# SCH_d_01_ex_01.net
KiCad netlist of a schematic drawn in EasyEDA
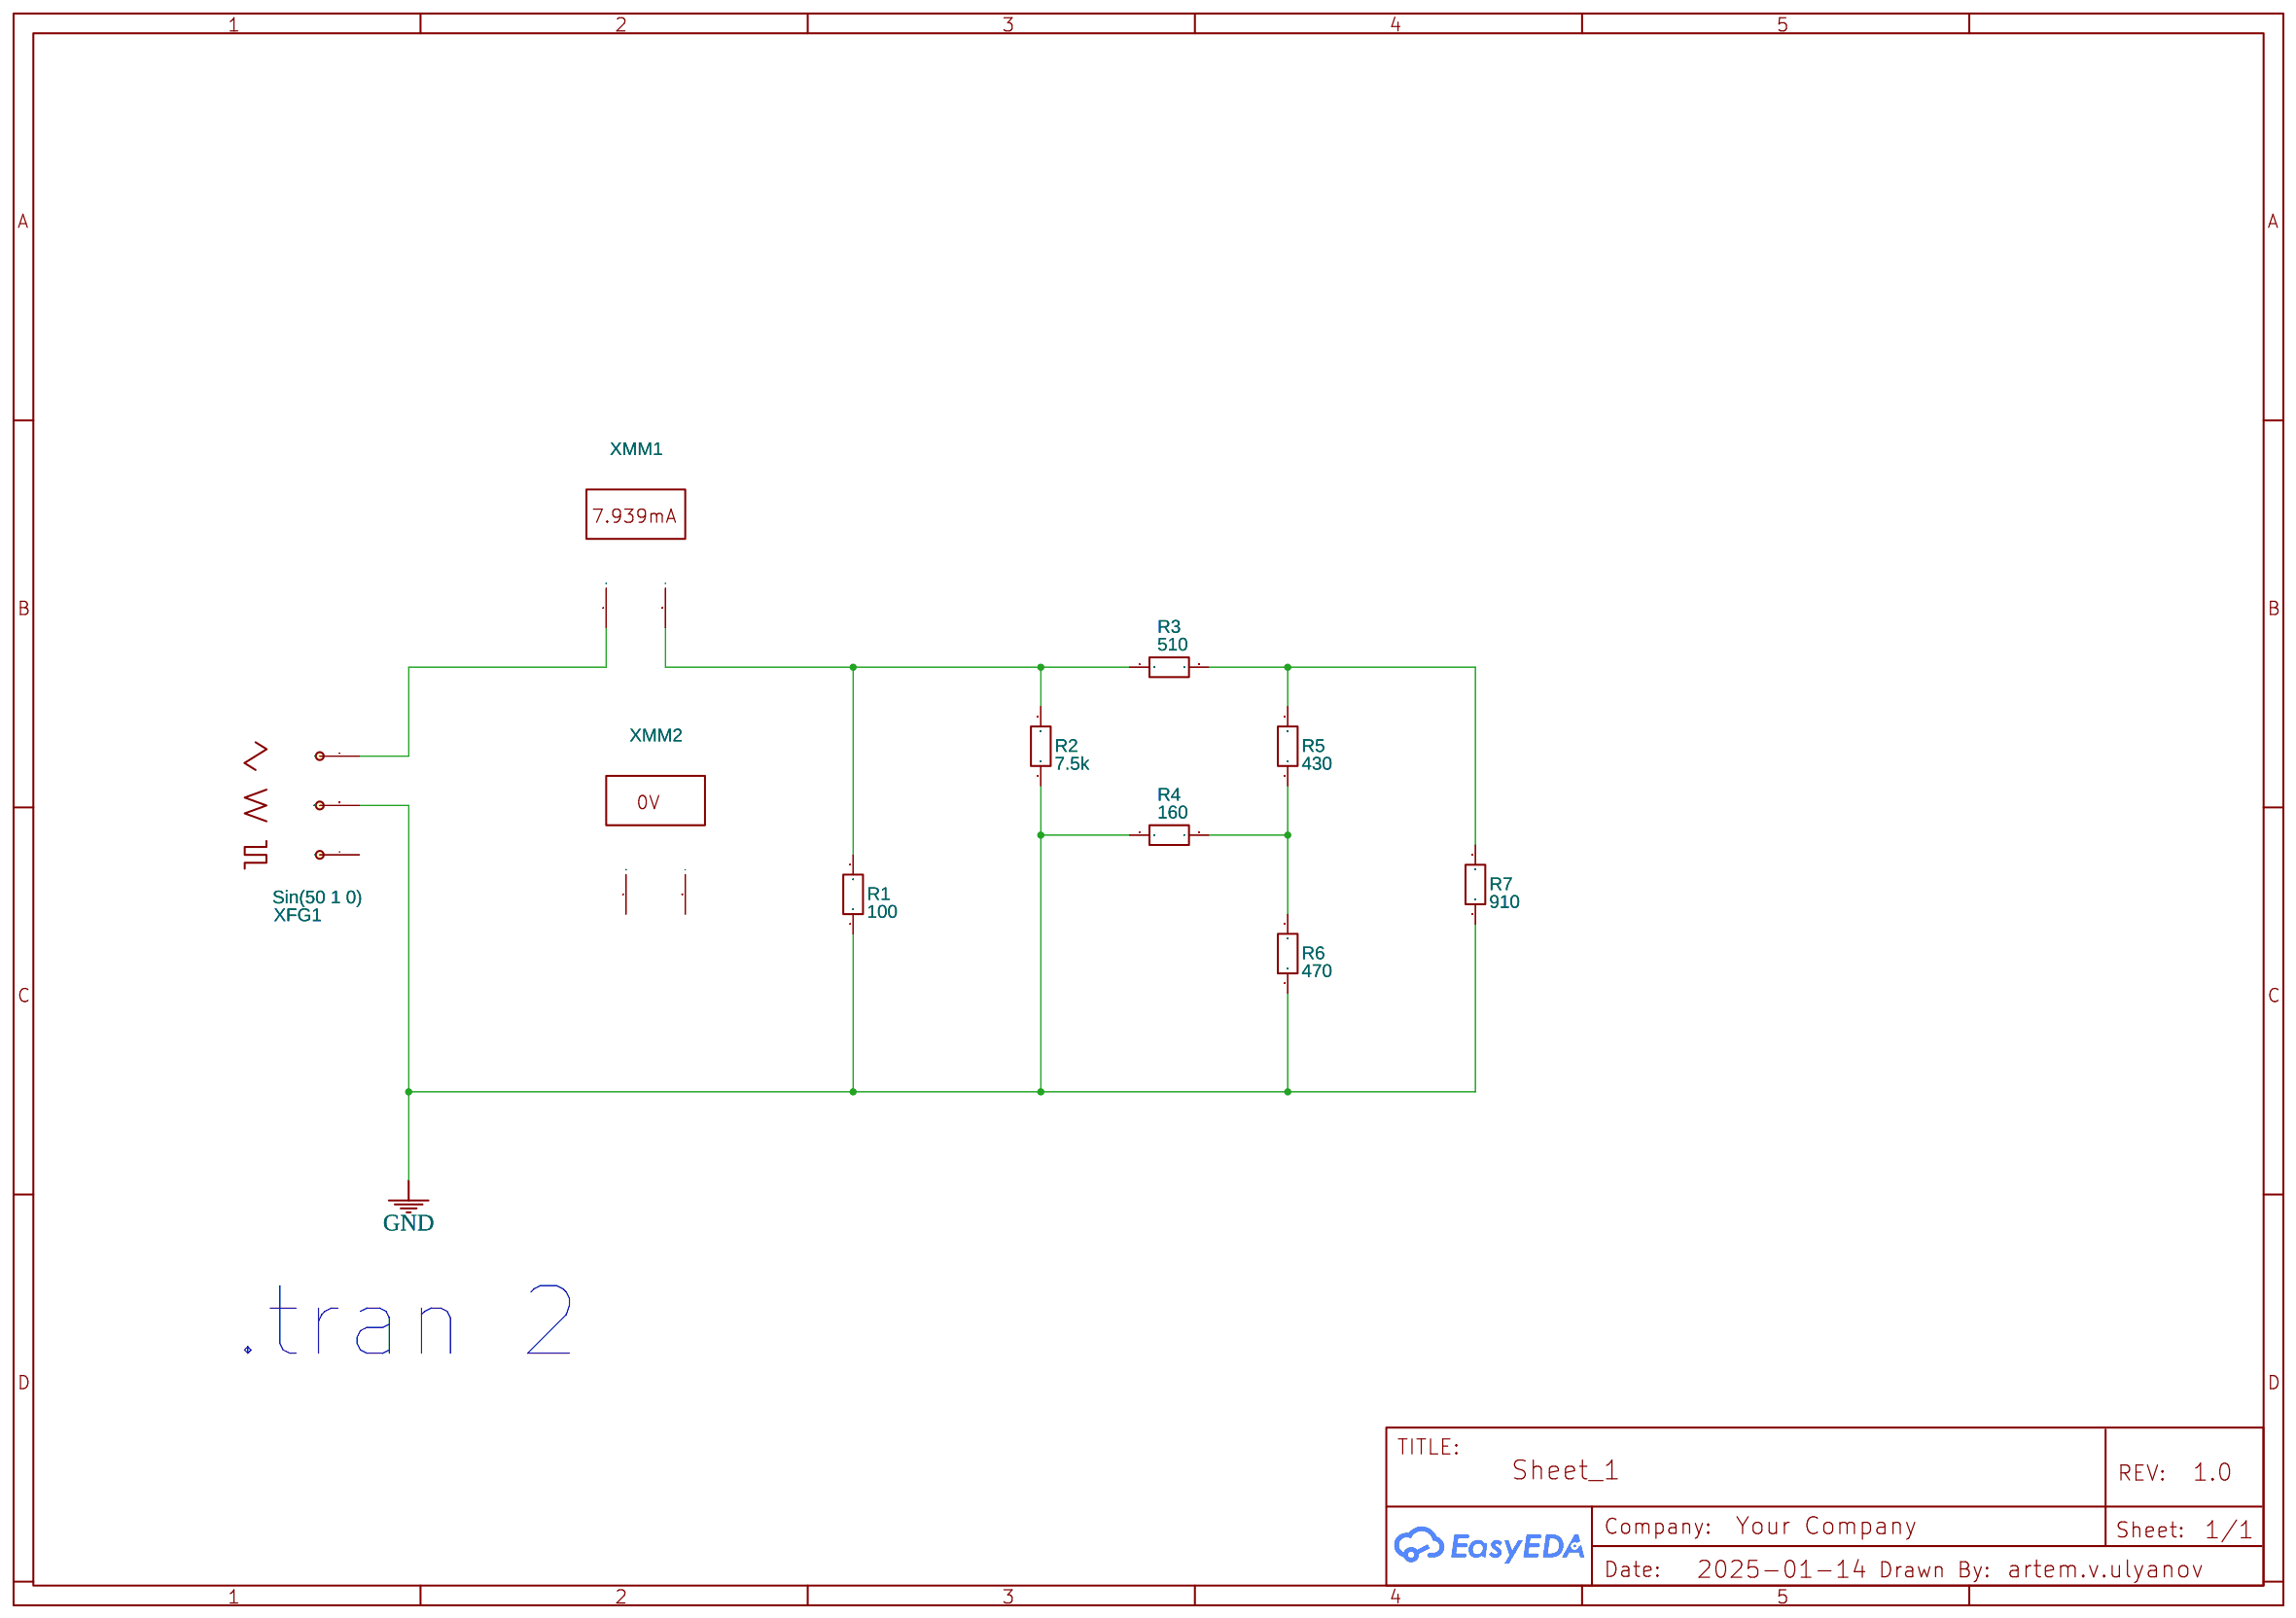
[diagram p0: EX01_0]
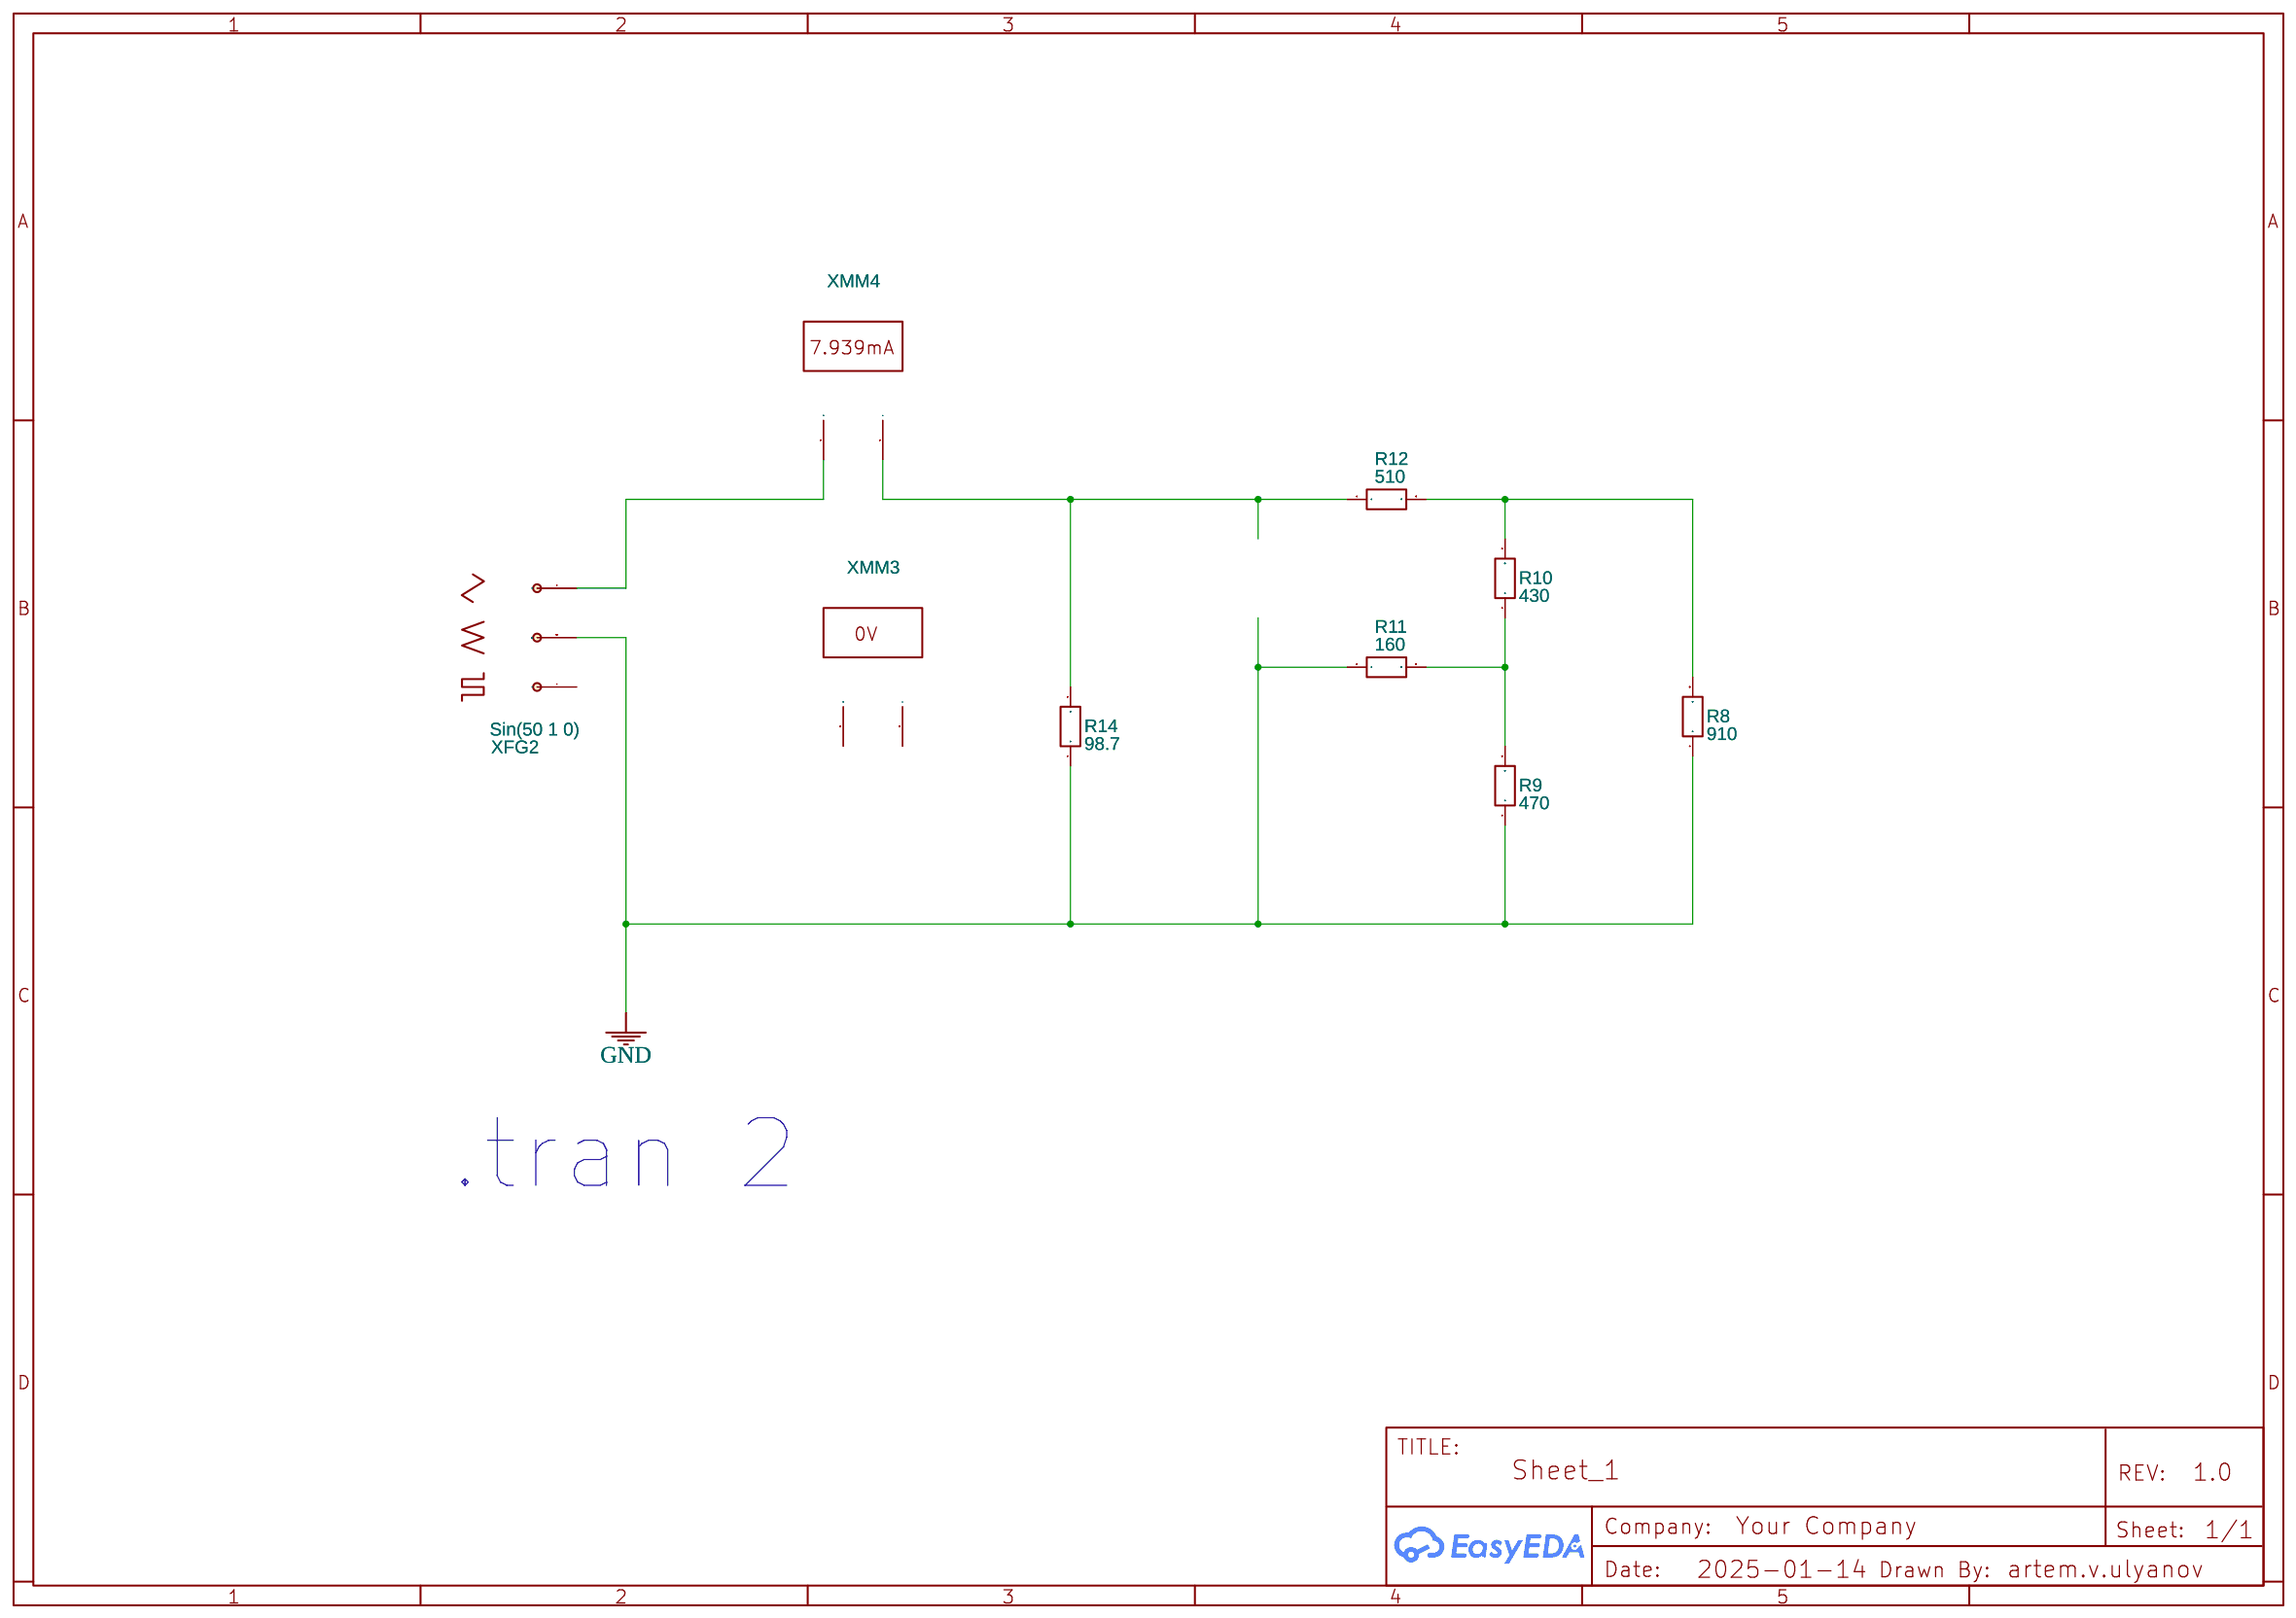
[diagram p1: EX01_1]
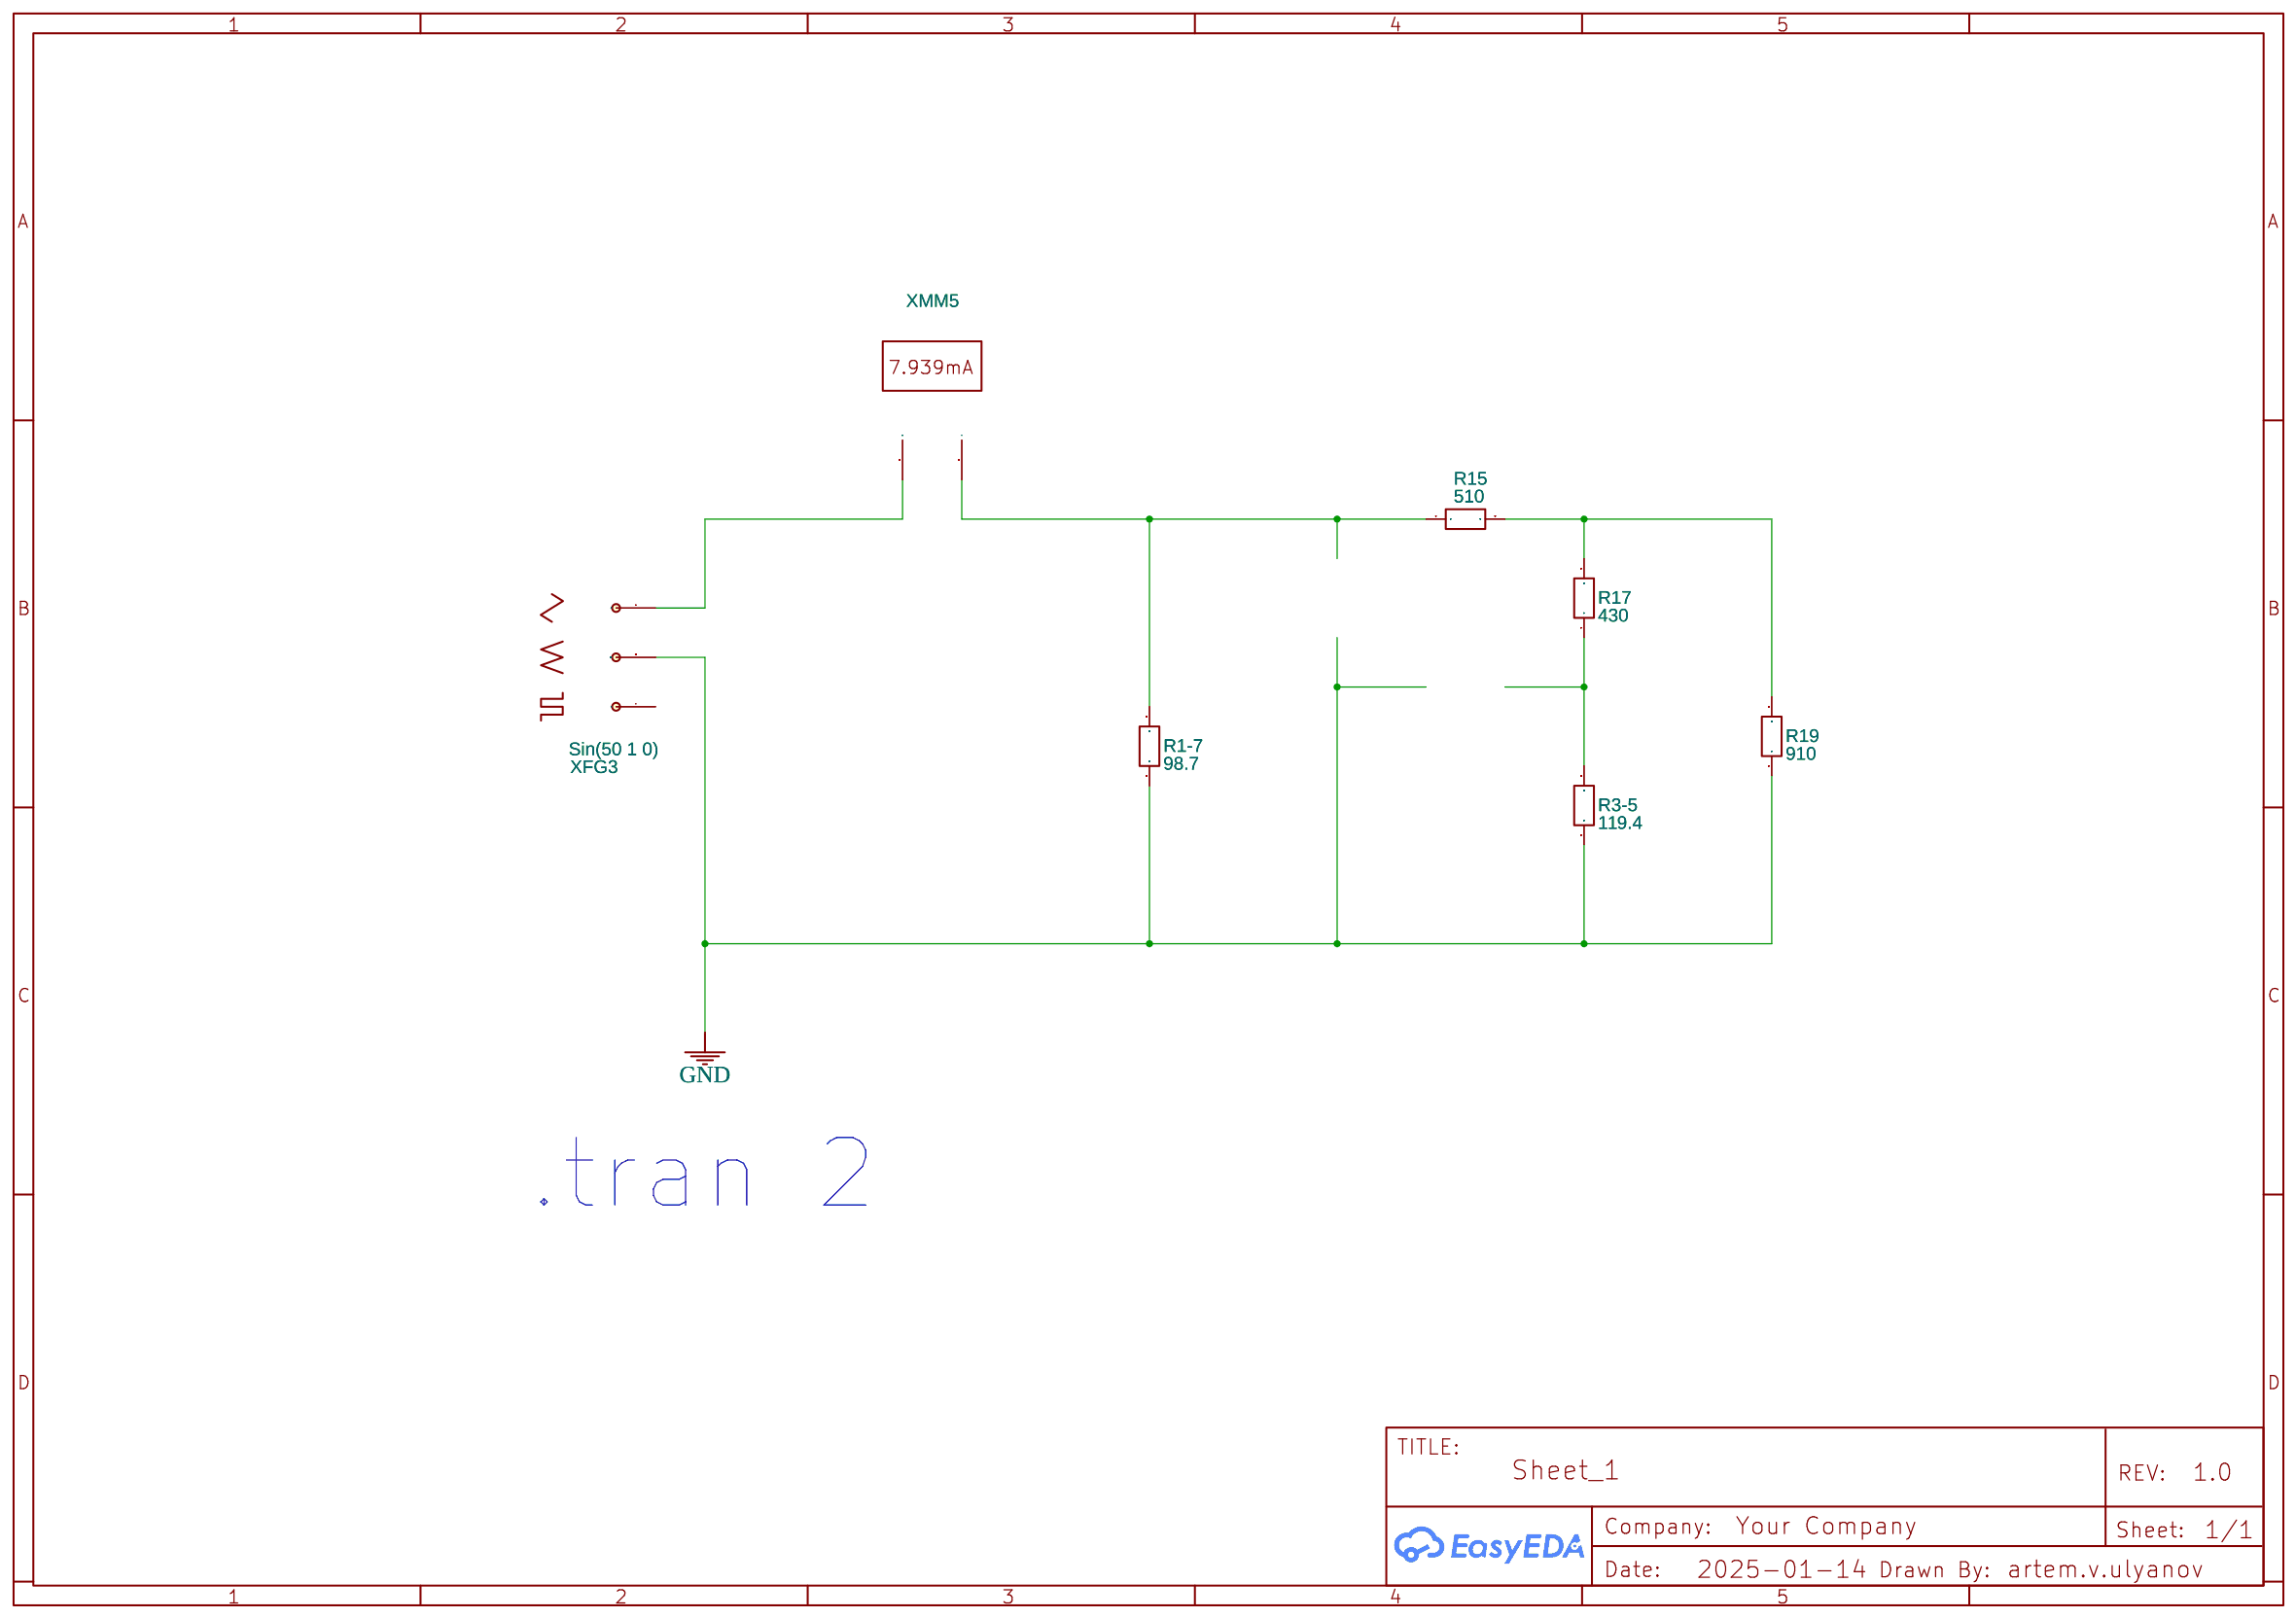
[diagram p2: EX01_2]
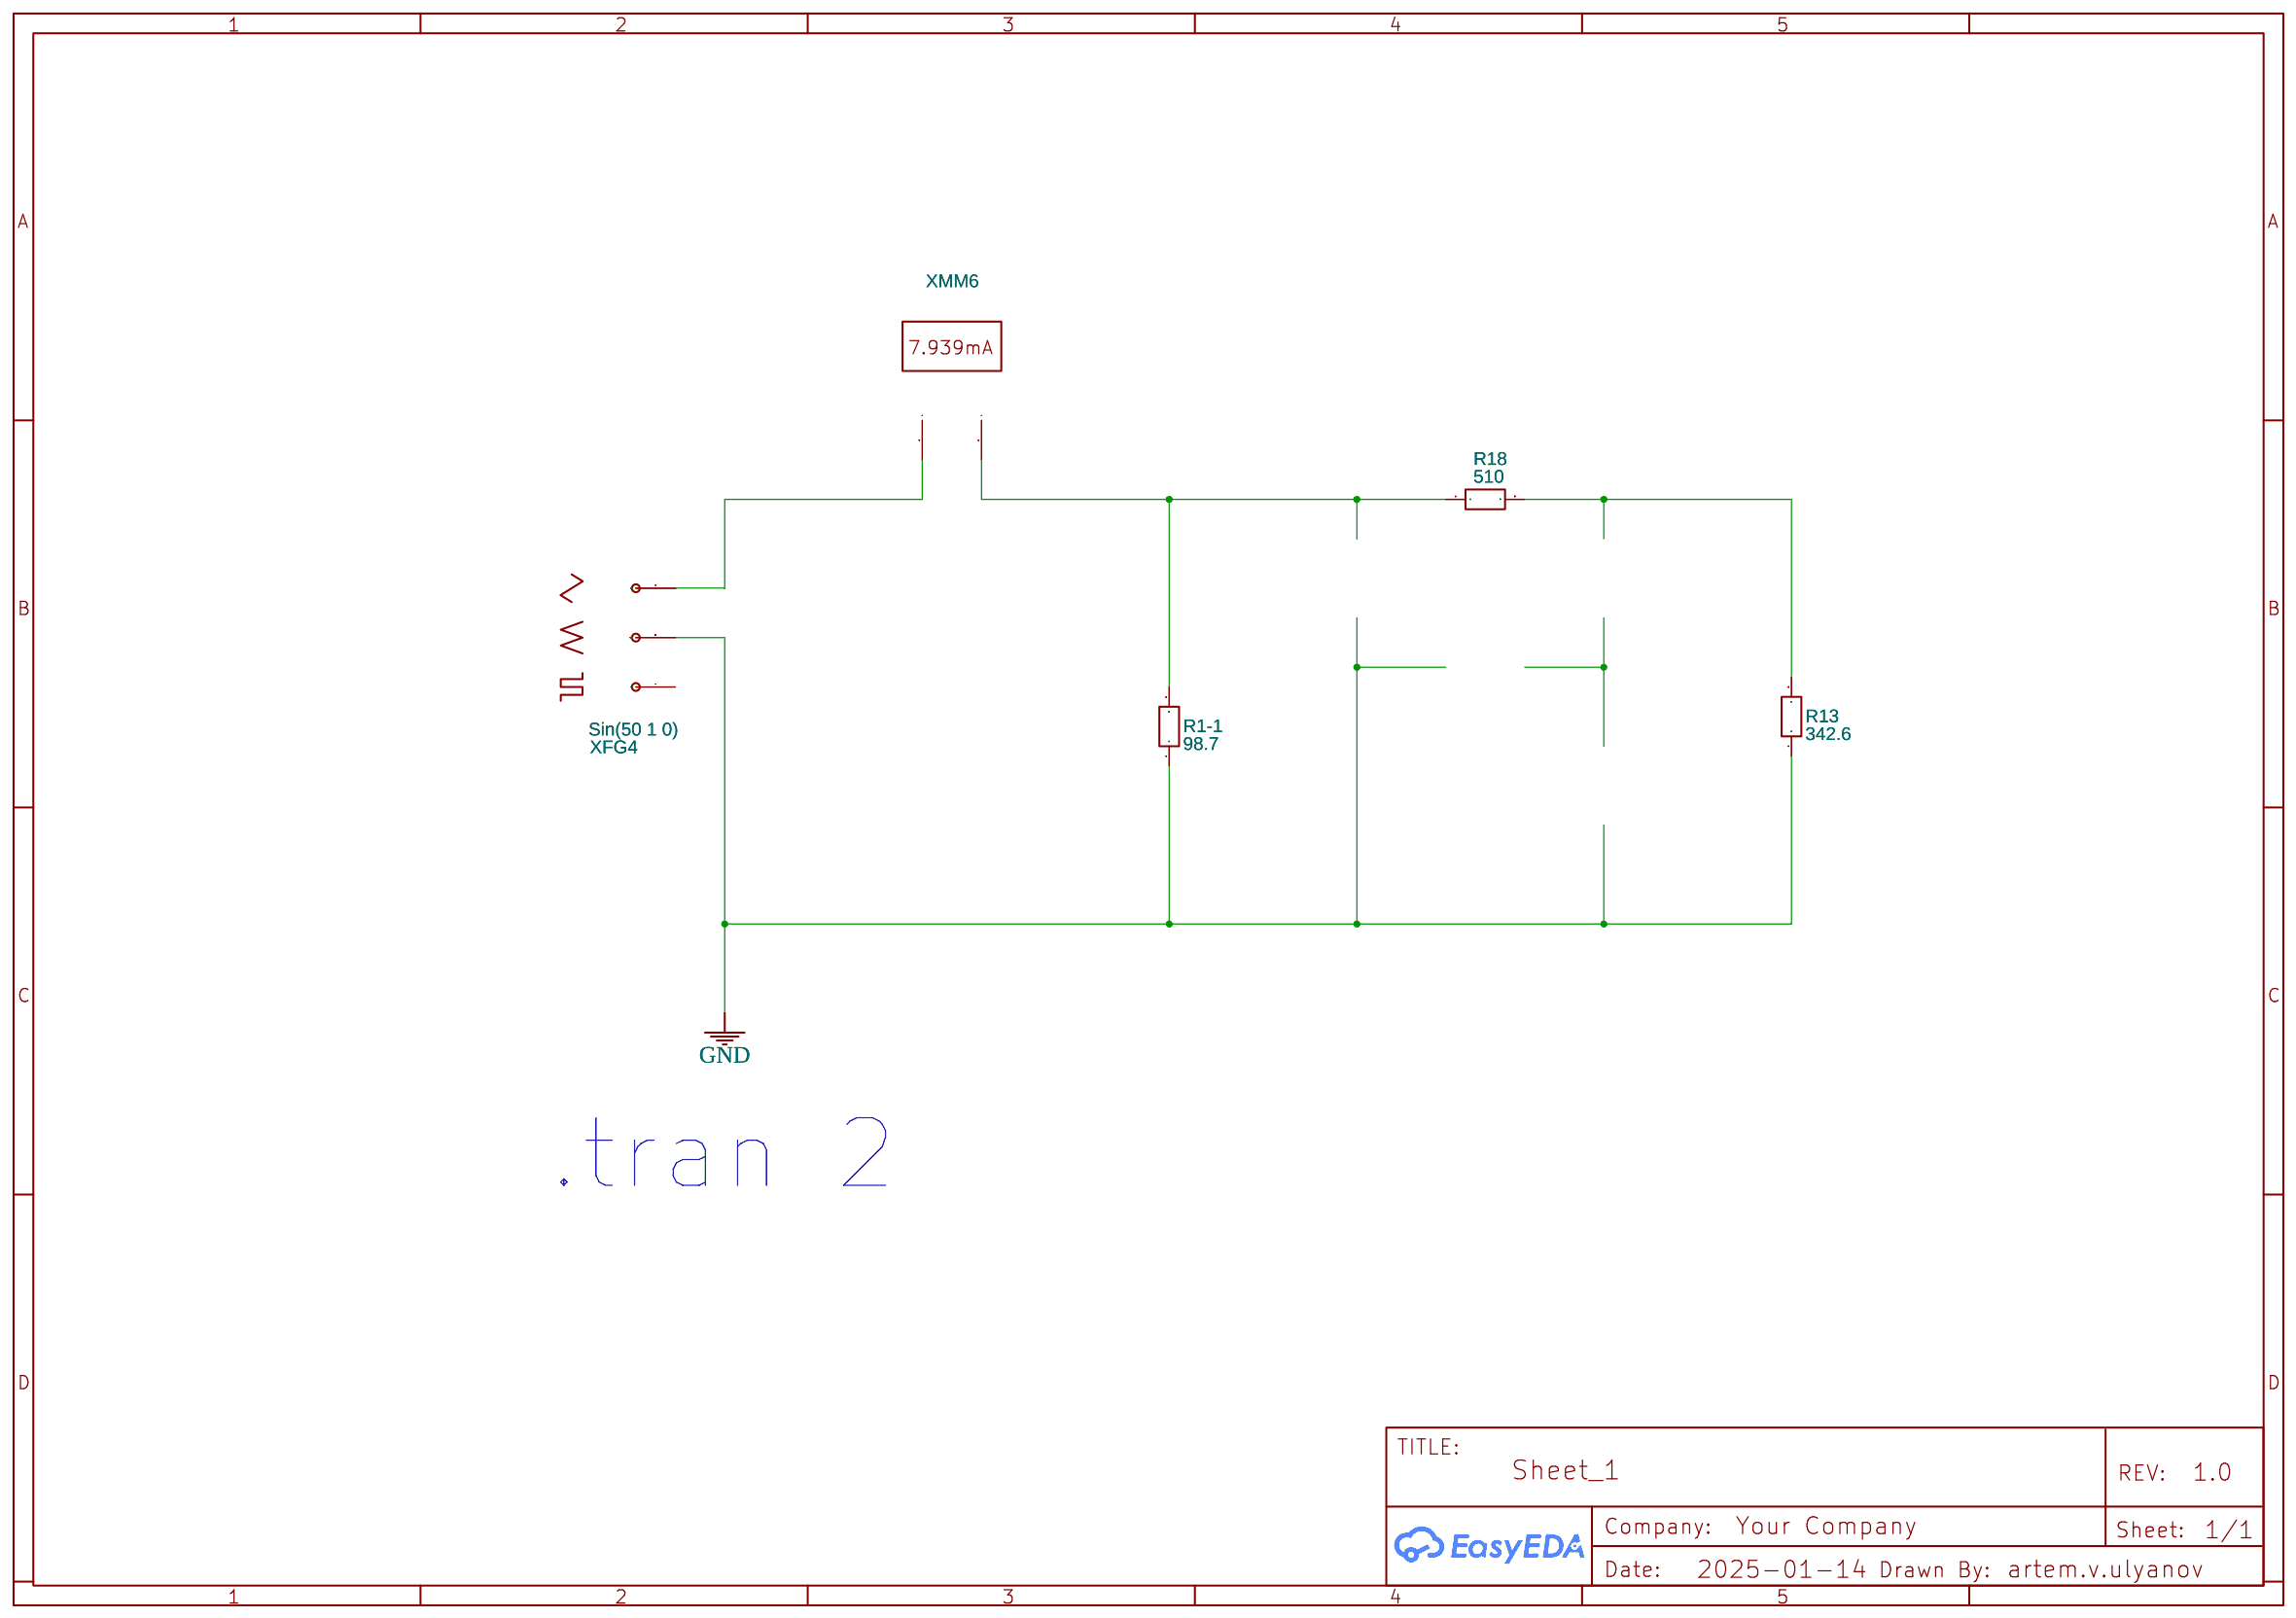
[diagram p3: EX01_3]
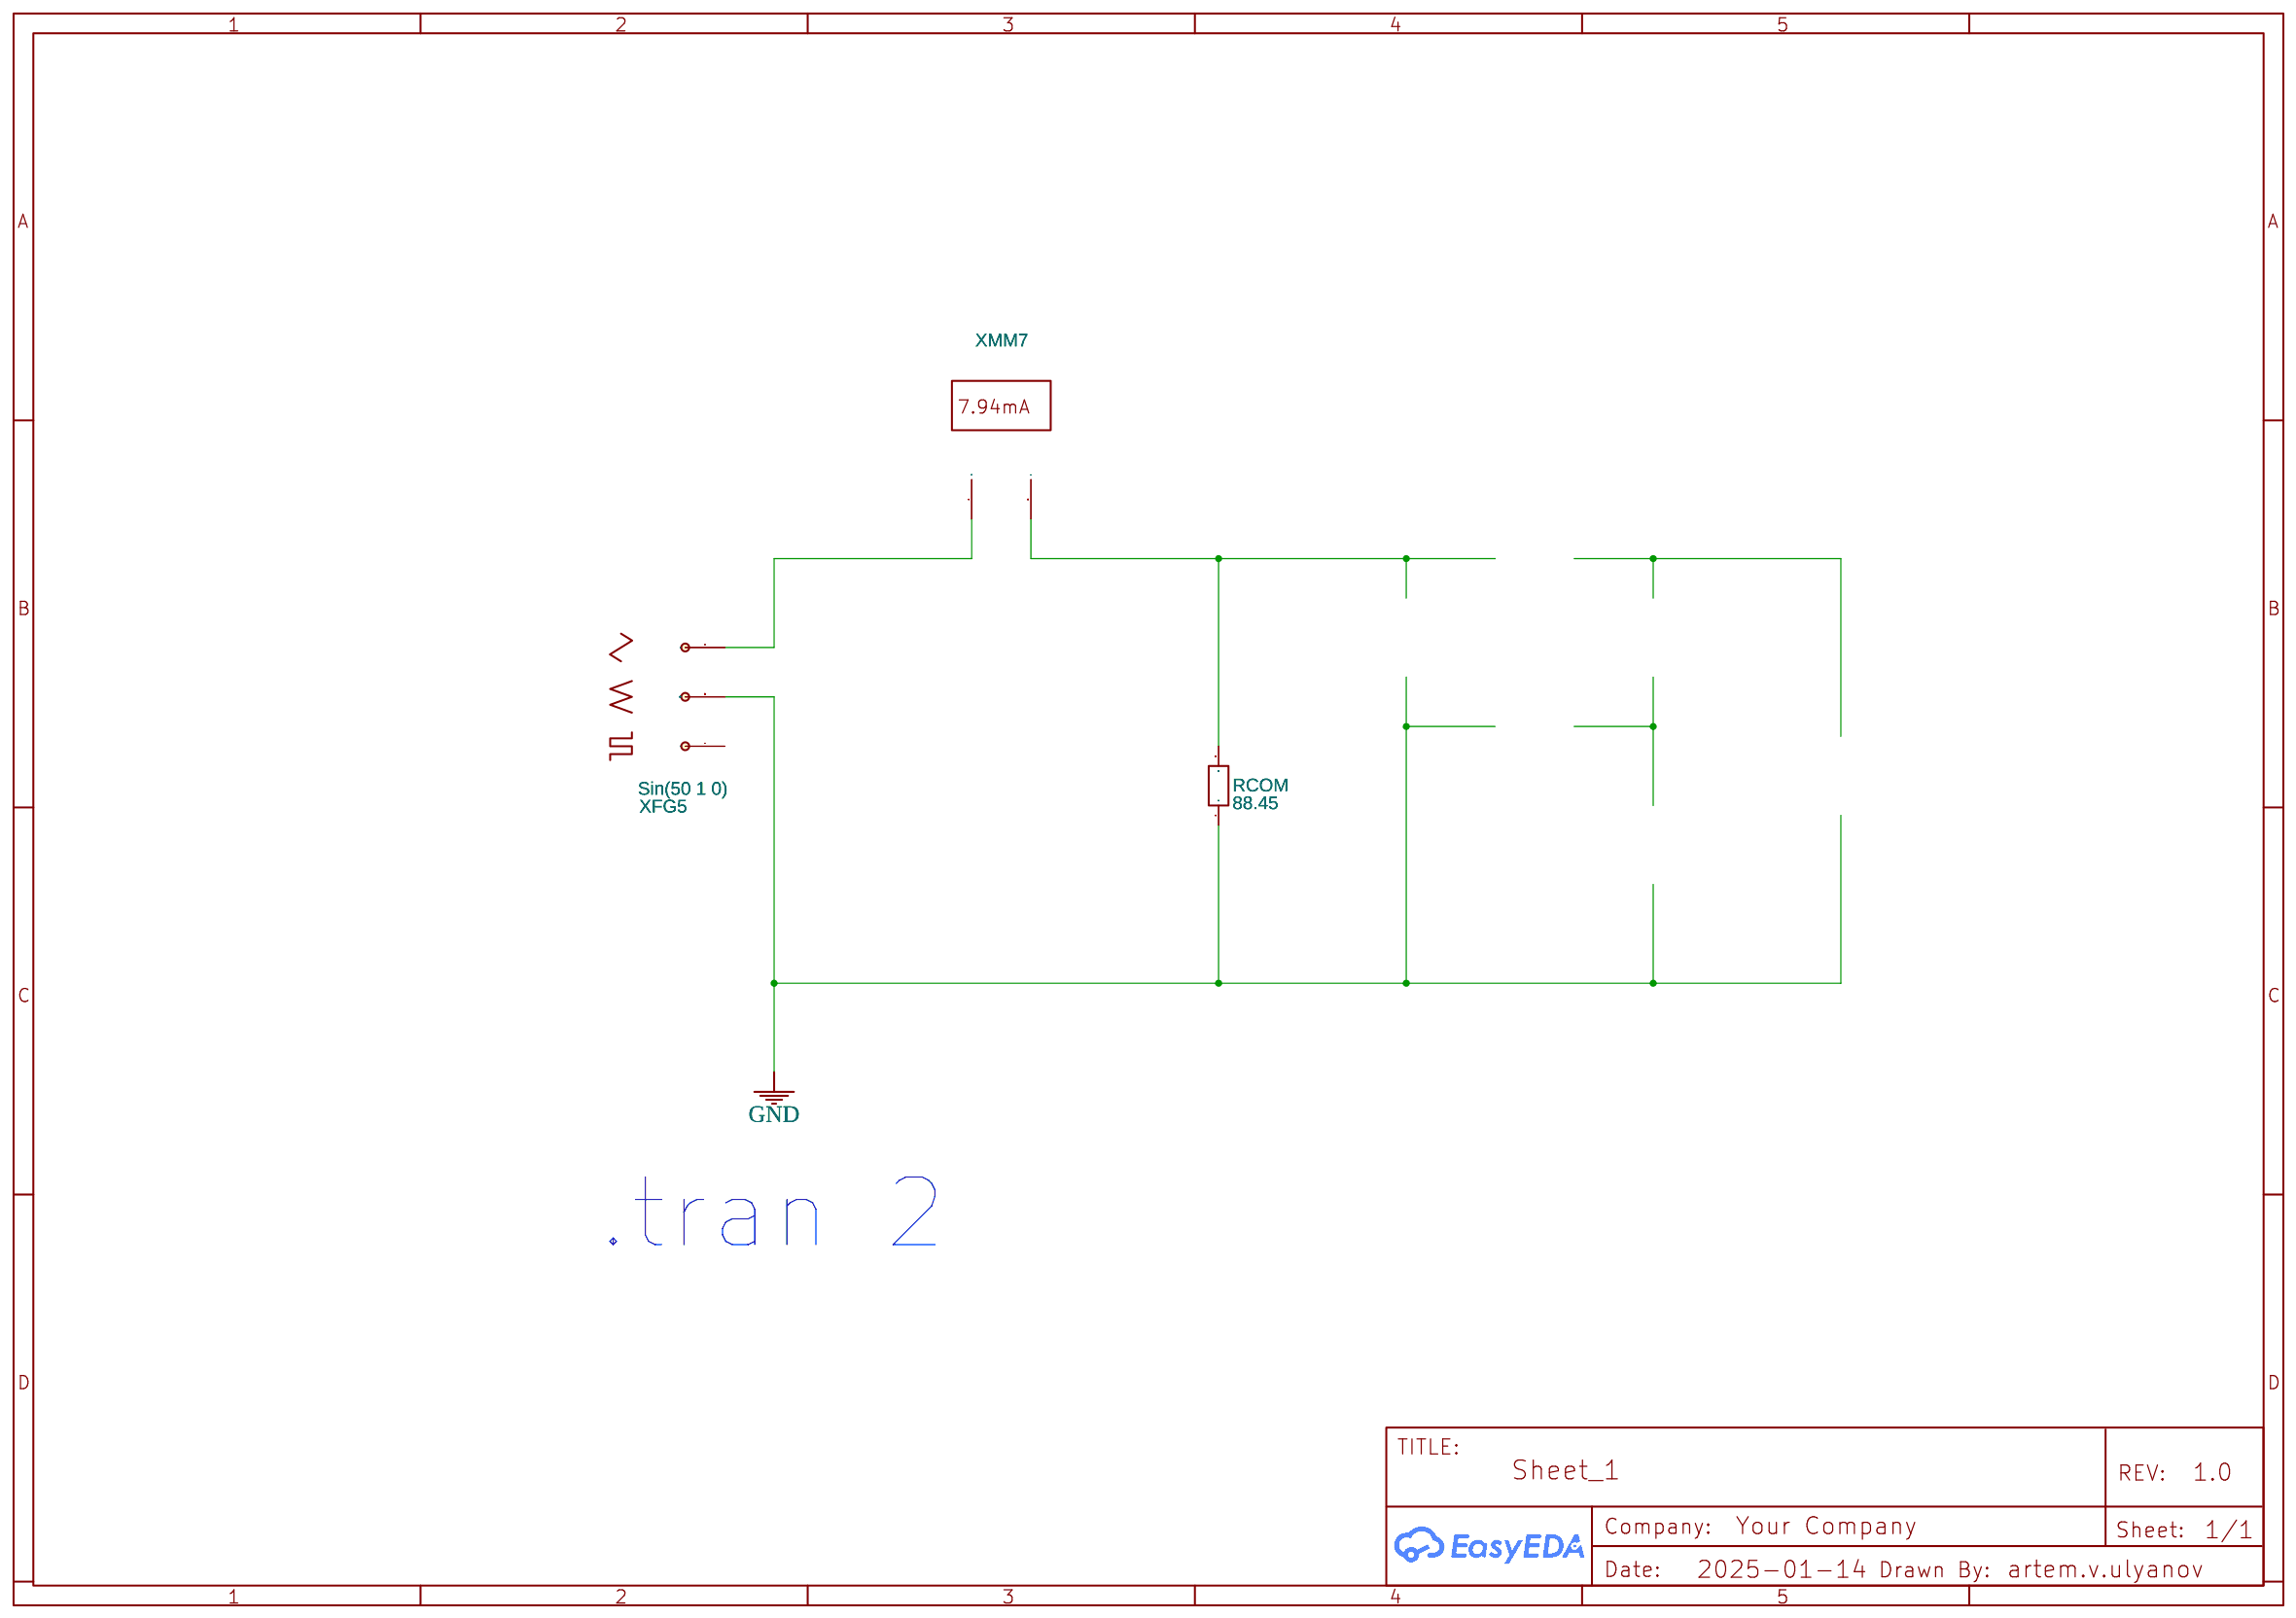
[diagram p4: EX01_4]

(export (version "E")
  (design (tool "Eeschema 10.0.6"))
  (components
    (comp (ref "R1") (value "100") (libsource (lib "") (part "R_0603_EU")))
    (comp (ref "R2") (value "7.5k") (libsource (lib "") (part "R_0603_EU")))
    (comp (ref "R3") (value "510") (libsource (lib "") (part "R_0603_EU_1")))
    (comp (ref "R4") (value "160") (libsource (lib "") (part "R_0603_EU_1")))
    (comp (ref "R5") (value "430") (libsource (lib "") (part "R_0603_EU")))
    (comp (ref "R6") (value "470") (libsource (lib "") (part "R_0603_EU")))
    (comp (ref "R7") (value "910") (libsource (lib "") (part "R_0603_EU")))
    (comp (ref "XFG1") (value "Sin(50 1 0)") (libsource (lib "") (part "FUNCTIONGENERATOR")))
    (comp (ref "XMM1") (value "Multimeter") (libsource (lib "") (part "MULTIMETER_1")))
    (comp (ref "XMM2") (value "Multimeter") (libsource (lib "") (part "MULTIMETER")))
    (comp (ref "R8") (value "910") (libsource (lib "") (part "R_0603_EU_1")))
    (comp (ref "R9") (value "470") (libsource (lib "") (part "R_0603_EU_1")))
    (comp (ref "R10") (value "430") (libsource (lib "") (part "R_0603_EU_1")))
    (comp (ref "R11") (value "160") (libsource (lib "") (part "R_0603_EU")))
    (comp (ref "R12") (value "510") (libsource (lib "") (part "R_0603_EU")))
    (comp (ref "R14") (value "98.7") (libsource (lib "") (part "R_0603_EU_1")))
    (comp (ref "XFG2") (value "Sin(50 1 0)") (libsource (lib "") (part "FUNCTIONGENERATOR")))
    (comp (ref "XMM3") (value "Multimeter") (libsource (lib "") (part "MULTIMETER_1")))
    (comp (ref "XMM4") (value "Multimeter") (libsource (lib "") (part "MULTIMETER")))
    (comp (ref "R1-7") (value "98.7") (libsource (lib "") (part "R_0603_EU")))
    (comp (ref "R3-5") (value "119.4") (libsource (lib "") (part "R_0603_EU_2")))
    (comp (ref "R15") (value "510") (libsource (lib "") (part "R_0603_EU_1")))
    (comp (ref "R17") (value "430") (libsource (lib "") (part "R_0603_EU_3")))
    (comp (ref "R19") (value "910") (libsource (lib "") (part "R_0603_EU_3")))
    (comp (ref "XFG3") (value "Sin(50 1 0)") (libsource (lib "") (part "FUNCTIONGENERATOR")))
    (comp (ref "XMM5") (value "Multimeter") (libsource (lib "") (part "MULTIMETER")))
    (comp (ref "R1-1") (value "98.7") (libsource (lib "") (part "R_0603_EU_2")))
    (comp (ref "R13") (value "342.6") (libsource (lib "") (part "R_0603_EU_1")))
    (comp (ref "R18") (value "510") (libsource (lib "") (part "R_0603_EU")))
    (comp (ref "XFG4") (value "Sin(50 1 0)") (libsource (lib "") (part "FUNCTIONGENERATOR")))
    (comp (ref "XMM6") (value "Multimeter") (libsource (lib "") (part "MULTIMETER")))
    (comp (ref "RCOM") (value "88.45") (libsource (lib "") (part "R_0603_EU")))
    (comp (ref "XFG5") (value "Sin(50 1 0)") (libsource (lib "") (part "FUNCTIONGENERATOR")))
    (comp (ref "XMM7") (value "Multimeter") (libsource (lib "") (part "MULTIMETER")))
  )
  (nets
    (net (code "1") (name "GND") (class "Default")
      (node (ref "R1") (pin "1") (pinfunction "1_1") (pintype "unspecified"))
      (node (ref "R1-1") (pin "1") (pinfunction "1_1") (pintype "unspecified"))
      (node (ref "R1-7") (pin "1") (pinfunction "1_1") (pintype "unspecified"))
      (node (ref "R11") (pin "1") (pinfunction "1_1") (pintype "unspecified"))
      (node (ref "R13") (pin "1") (pinfunction "1_1") (pintype "unspecified"))
      (node (ref "R14") (pin "1") (pinfunction "1_1") (pintype "unspecified"))
      (node (ref "R19") (pin "1") (pinfunction "1_1") (pintype "unspecified"))
      (node (ref "R2") (pin "1") (pinfunction "1_1") (pintype "unspecified"))
      (node (ref "R3-5") (pin "1") (pinfunction "1_1") (pintype "unspecified"))
      (node (ref "R4") (pin "1") (pinfunction "1_1") (pintype "unspecified"))
      (node (ref "R6") (pin "1") (pinfunction "1_1") (pintype "unspecified"))
      (node (ref "R7") (pin "1") (pinfunction "1_1") (pintype "unspecified"))
      (node (ref "R8") (pin "1") (pinfunction "1_1") (pintype "unspecified"))
      (node (ref "R9") (pin "1") (pinfunction "1_1") (pintype "unspecified"))
      (node (ref "RCOM") (pin "1") (pinfunction "1_1") (pintype "unspecified"))
      (node (ref "XFG1") (pin "COM") (pinfunction "COM_COM") (pintype "unspecified"))
      (node (ref "XFG2") (pin "COM") (pinfunction "COM_COM") (pintype "unspecified"))
      (node (ref "XFG3") (pin "COM") (pinfunction "COM_COM") (pintype "unspecified"))
      (node (ref "XFG4") (pin "COM") (pinfunction "COM_COM") (pintype "unspecified"))
      (node (ref "XFG5") (pin "COM") (pinfunction "COM_COM") (pintype "unspecified"))
    )
    (net (code "2") (name "Net-(R3-Pad2)") (class "Default")
      (node (ref "R3") (pin "2") (pinfunction "2_2") (pintype "unspecified"))
      (node (ref "R5") (pin "2") (pinfunction "2_2") (pintype "unspecified"))
      (node (ref "R7") (pin "2") (pinfunction "2_2") (pintype "unspecified"))
    )
    (net (code "3") (name "Net-(R4-Pad2)") (class "Default")
      (node (ref "R4") (pin "2") (pinfunction "2_2") (pintype "unspecified"))
      (node (ref "R5") (pin "1") (pinfunction "1_1") (pintype "unspecified"))
      (node (ref "R6") (pin "2") (pinfunction "2_2") (pintype "unspecified"))
    )
    (net (code "4") (name "Net-(R10-Pad1)") (class "Default")
      (node (ref "R10") (pin "1") (pinfunction "1_1") (pintype "unspecified"))
      (node (ref "R11") (pin "2") (pinfunction "2_2") (pintype "unspecified"))
      (node (ref "R9") (pin "2") (pinfunction "2_2") (pintype "unspecified"))
    )
    (net (code "5") (name "Net-(R10-Pad2)") (class "Default")
      (node (ref "R10") (pin "2") (pinfunction "2_2") (pintype "unspecified"))
      (node (ref "R12") (pin "2") (pinfunction "2_2") (pintype "unspecified"))
      (node (ref "R8") (pin "2") (pinfunction "2_2") (pintype "unspecified"))
    )
    (net (code "6") (name "Net-(R13-Pad2)") (class "Default")
      (node (ref "R13") (pin "2") (pinfunction "2_2") (pintype "unspecified"))
      (node (ref "R18") (pin "2") (pinfunction "2_2") (pintype "unspecified"))
    )
    (net (code "7") (name "Net-(R15-Pad2)") (class "Default")
      (node (ref "R15") (pin "2") (pinfunction "2_2") (pintype "unspecified"))
      (node (ref "R17") (pin "2") (pinfunction "2_2") (pintype "unspecified"))
      (node (ref "R19") (pin "2") (pinfunction "2_2") (pintype "unspecified"))
    )
    (net (code "8") (name "Net-(R17-Pad1)") (class "Default")
      (node (ref "R17") (pin "1") (pinfunction "1_1") (pintype "unspecified"))
      (node (ref "R3-5") (pin "2") (pinfunction "2_2") (pintype "unspecified"))
    )
    (net (code "9") (name "Net-(XMM1-+)") (class "Default")
      (node (ref "XFG1") (pin "+") (pinfunction "+_+") (pintype "unspecified"))
      (node (ref "XMM1") (pin "1") (pinfunction "+_1") (pintype "unspecified"))
    )
    (net (code "10") (name "Net-(XMM1-I)") (class "Default")
      (node (ref "R1") (pin "2") (pinfunction "2_2") (pintype "unspecified"))
      (node (ref "R2") (pin "2") (pinfunction "2_2") (pintype "unspecified"))
      (node (ref "R3") (pin "1") (pinfunction "1_1") (pintype "unspecified"))
      (node (ref "XMM1") (pin "2") (pinfunction "I_2") (pintype "unspecified"))
    )
    (net (code "11") (name "Net-(XMM4-+)") (class "Default")
      (node (ref "XFG2") (pin "+") (pinfunction "+_+") (pintype "unspecified"))
      (node (ref "XMM4") (pin "1") (pinfunction "+_1") (pintype "unspecified"))
    )
    (net (code "12") (name "Net-(XMM4-I)") (class "Default")
      (node (ref "R12") (pin "1") (pinfunction "1_1") (pintype "unspecified"))
      (node (ref "R14") (pin "2") (pinfunction "2_2") (pintype "unspecified"))
      (node (ref "XMM4") (pin "2") (pinfunction "I_2") (pintype "unspecified"))
    )
    (net (code "13") (name "Net-(XMM5-+)") (class "Default")
      (node (ref "XFG3") (pin "+") (pinfunction "+_+") (pintype "unspecified"))
      (node (ref "XMM5") (pin "1") (pinfunction "+_1") (pintype "unspecified"))
    )
    (net (code "14") (name "Net-(XMM5-I)") (class "Default")
      (node (ref "R1-7") (pin "2") (pinfunction "2_2") (pintype "unspecified"))
      (node (ref "R15") (pin "1") (pinfunction "1_1") (pintype "unspecified"))
      (node (ref "XMM5") (pin "2") (pinfunction "I_2") (pintype "unspecified"))
    )
    (net (code "15") (name "Net-(XMM6-+)") (class "Default")
      (node (ref "XFG4") (pin "+") (pinfunction "+_+") (pintype "unspecified"))
      (node (ref "XMM6") (pin "1") (pinfunction "+_1") (pintype "unspecified"))
    )
    (net (code "16") (name "Net-(XMM6-I)") (class "Default")
      (node (ref "R1-1") (pin "2") (pinfunction "2_2") (pintype "unspecified"))
      (node (ref "R18") (pin "1") (pinfunction "1_1") (pintype "unspecified"))
      (node (ref "XMM6") (pin "2") (pinfunction "I_2") (pintype "unspecified"))
    )
    (net (code "17") (name "Net-(XMM7-+)") (class "Default")
      (node (ref "XFG5") (pin "+") (pinfunction "+_+") (pintype "unspecified"))
      (node (ref "XMM7") (pin "1") (pinfunction "+_1") (pintype "unspecified"))
    )
    (net (code "18") (name "Net-(XMM7-I)") (class "Default")
      (node (ref "RCOM") (pin "2") (pinfunction "2_2") (pintype "unspecified"))
      (node (ref "XMM7") (pin "2") (pinfunction "I_2") (pintype "unspecified"))
    )
    (net (code "19") (name "unconnected-(XFG1-Pad-)") (class "Default")
      (node (ref "XFG1") (pin "-") (pinfunction "-_-") (pintype "unspecified"))
    )
    (net (code "20") (name "unconnected-(XFG2-Pad-)") (class "Default")
      (node (ref "XFG2") (pin "-") (pinfunction "-_-") (pintype "unspecified"))
    )
    (net (code "21") (name "unconnected-(XFG3-Pad-)") (class "Default")
      (node (ref "XFG3") (pin "-") (pinfunction "-_-") (pintype "unspecified"))
    )
    (net (code "22") (name "unconnected-(XFG4-Pad-)") (class "Default")
      (node (ref "XFG4") (pin "-") (pinfunction "-_-") (pintype "unspecified"))
    )
    (net (code "23") (name "unconnected-(XFG5-Pad-)") (class "Default")
      (node (ref "XFG5") (pin "-") (pinfunction "-_-") (pintype "unspecified"))
    )
    (net (code "24") (name "unconnected-(XMM2-+-Pad1)") (class "Default")
      (node (ref "XMM2") (pin "1") (pinfunction "+_1") (pintype "unspecified"))
    )
    (net (code "25") (name "unconnected-(XMM2-I-Pad2)") (class "Default")
      (node (ref "XMM2") (pin "2") (pinfunction "I_2") (pintype "unspecified"))
    )
    (net (code "26") (name "unconnected-(XMM3-+-Pad1)") (class "Default")
      (node (ref "XMM3") (pin "1") (pinfunction "+_1") (pintype "unspecified"))
    )
    (net (code "27") (name "unconnected-(XMM3-I-Pad2)") (class "Default")
      (node (ref "XMM3") (pin "2") (pinfunction "I_2") (pintype "unspecified"))
    )
  )
)
